# HFM_Can_AX_Eeprom_V1.net
KiCad netlist of a schematic drawn in Altium Designer
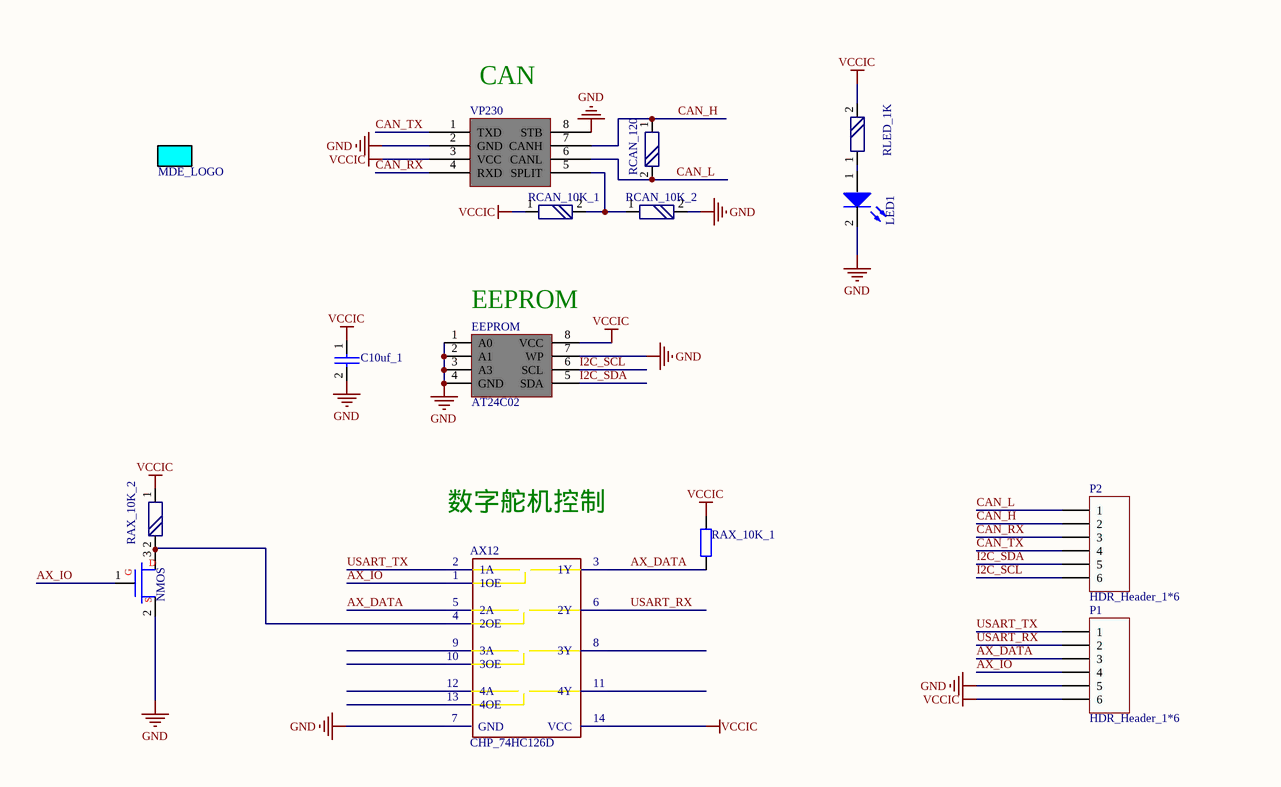
[diagram p0: HFM_Can_AX_Eeprom_V1.SchDoc, left]
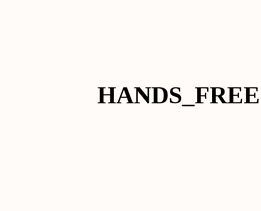
[diagram p1: HFM_Can_AX_Eeprom_V1.SchDoc, right]

(export (version "E")
  (design (tool "Eeschema 10.0.6"))
  (components
    (comp (ref "*")
      (value "MDE_LOGO")
      (footprint "MDE_LOGO_Overlay")
      (libsource (lib "Hands_free") (part "MDE_LOGO"))
    )
    (comp (ref "AX12")
      (value "CHP_74HC126D")
      (footprint "CHP_SOP_14P")
      (description "4路三态门缓冲器")
      (libsource (lib "HANDS-FREEE-PcbLib-V1.01") (part "CHP_74HC126D"))
    )
    (comp (ref "C10uf_1")
      (value "ELE_Cap_10uf")
      (footprint "ELE_0805_P")
      (description "电容10uf固定")
      (libsource (lib "HANDS-FREEE-PcbLib-V1.01") (part "ELE_Cap_10uf"))
    )
    (comp (ref "EEPROM")
      (value "AT24C02")
      (footprint "CHP_SOP_8P")
      (description "Polarized Capacitor (Radial)")
      (fields (field (name "PUBLISHER") "Altium Limited"))
      (libsource (lib "Hands_free") (part "CHP_AT24C0X"))
    )
    (comp (ref "LED1")
      (value "ELE_LED")
      (footprint "ELE_0805极性_P")
      (description "发光二极管")
      (fields (field (name "PUBLISHER") "Altium Limited"))
      (libsource (lib "Hands_free") (part "ELE_LED"))
    )
    (comp (ref "NMOS")
      (value "SIS412DN")
      (footprint "CHP_SOT23_P_3P")
      (description "MOS管")
      (fields (field (name "PUBLISHER") "Altium Limited"))
      (libsource (lib "Hands_free") (part "ELE_NMOS_1"))
    )
    (comp (ref "P1")
      (value "HDR_Header_1*6")
      (footprint "HDR_STAMPHOLE_2.00_DH_1*6")
      (fields (field (name "PUBLISHER") "Altium Limited"))
      (libsource (lib "HANDS-FREEE-PcbLib-V1.01") (part "HDR_Header_1*6"))
    )
    (comp (ref "P2")
      (value "HDR_Header_1*6")
      (footprint "HDR_STAMPHOLE_2.00_DH_1*6")
      (fields (field (name "PUBLISHER") "Altium Limited"))
      (libsource (lib "HANDS-FREEE-PcbLib-V1.01") (part "HDR_Header_1*6"))
    )
    (comp (ref "RAX_10K_1")
      (value "Res2")
      (footprint "ELE_0805_P")
      (description "Resistor")
      (fields (field (name "PUBLISHER") "Altium Limited"))
      (libsource (lib "Miscellaneous Devices") (part "Res2"))
    )
    (comp (ref "RAX_10K_2")
      (value "ELE_RES_1")
      (footprint "ELE_0805_P")
      (description "电阻")
      (libsource (lib "Hands_free") (part "ELE_RES_1"))
    )
    (comp (ref "RCAN_10K_1")
      (value "ELE_RES_1")
      (footprint "ELE_0805_P")
      (description "电阻")
      (libsource (lib "Hands_free") (part "ELE_RES_1"))
    )
    (comp (ref "RCAN_10K_2")
      (value "ELE_RES_1")
      (footprint "ELE_0805_P")
      (description "电阻")
      (libsource (lib "Hands_free") (part "ELE_RES_1"))
    )
    (comp (ref "RCAN_120")
      (value "ELE_RES_1")
      (footprint "ELE_0805_P")
      (description "电阻")
      (libsource (lib "Hands_free") (part "ELE_RES_1"))
    )
    (comp (ref "RLED_1K")
      (value "ELE_RES_1")
      (footprint "ELE_0805_P")
      (description "电阻")
      (libsource (lib "Hands_free") (part "ELE_RES_1"))
    )
    (comp (ref "VP230")
      (value "CHP_VP230_P")
      (footprint "CHP_VP230_P")
      (libsource (lib "Hands_free") (part "CHP_VP230_P"))
    )
  )
  (nets
    (net (code "1") (name "/AX_DATA") (class "Default")
      (node (ref "AX12") (pin "3") (pinfunction "1Y_3") (pintype "passive"))
      (node (ref "AX12") (pin "5") (pinfunction "2A_5") (pintype "passive"))
      (node (ref "P1") (pin "3") (pinfunction "3_3") (pintype "passive"))
      (node (ref "RAX_10K_1") (pin "1") (pinfunction "1_1") (pintype "passive"))
    )
    (net (code "2") (name "/AX_IO") (class "Default")
      (node (ref "AX12") (pin "1") (pinfunction "1OE_1") (pintype "passive"))
      (node (ref "NMOS") (pin "1") (pinfunction "G_1") (pintype "passive"))
      (node (ref "P1") (pin "4") (pinfunction "4_4") (pintype "passive"))
    )
    (net (code "3") (name "/CAN_H") (class "Default")
      (node (ref "P2") (pin "2") (pinfunction "2_2") (pintype "passive"))
      (node (ref "RCAN_120") (pin "1") (pintype "passive"))
      (node (ref "VP230") (pin "7") (pinfunction "CANH_7") (pintype "passive"))
    )
    (net (code "4") (name "/CAN_L") (class "Default")
      (node (ref "P2") (pin "1") (pinfunction "1_1") (pintype "passive"))
      (node (ref "RCAN_120") (pin "2") (pintype "passive"))
      (node (ref "VP230") (pin "6") (pinfunction "CANL_6") (pintype "passive"))
    )
    (net (code "5") (name "/CAN_RX") (class "Default")
      (node (ref "P2") (pin "3") (pinfunction "3_3") (pintype "passive"))
      (node (ref "VP230") (pin "4") (pinfunction "RXD_4") (pintype "passive"))
    )
    (net (code "6") (name "/CAN_TX") (class "Default")
      (node (ref "P2") (pin "4") (pinfunction "4_4") (pintype "passive"))
      (node (ref "VP230") (pin "1") (pinfunction "TXD_1") (pintype "passive"))
    )
    (net (code "7") (name "/I2C_SCL") (class "Default")
      (node (ref "EEPROM") (pin "6") (pinfunction "SCL_6") (pintype "passive"))
      (node (ref "P2") (pin "6") (pinfunction "6_6") (pintype "passive"))
    )
    (net (code "8") (name "/I2C_SDA") (class "Default")
      (node (ref "EEPROM") (pin "5") (pinfunction "SDA_5") (pintype "passive"))
      (node (ref "P2") (pin "5") (pinfunction "5_5") (pintype "passive"))
    )
    (net (code "9") (name "/USART_RX") (class "Default")
      (node (ref "AX12") (pin "6") (pinfunction "2Y_6") (pintype "passive"))
      (node (ref "P1") (pin "2") (pinfunction "2_2") (pintype "passive"))
    )
    (net (code "10") (name "/USART_TX") (class "Default")
      (node (ref "AX12") (pin "2") (pinfunction "1A_2") (pintype "passive"))
      (node (ref "P1") (pin "1") (pinfunction "1_1") (pintype "passive"))
    )
    (net (code "11") (name "GND") (class "Default")
      (node (ref "AX12") (pin "7") (pinfunction "GND_7") (pintype "passive"))
      (node (ref "C10uf_1") (pin "2") (pintype "passive"))
      (node (ref "EEPROM") (pin "1") (pinfunction "A0_1") (pintype "passive"))
      (node (ref "EEPROM") (pin "2") (pinfunction "A1_2") (pintype "passive"))
      (node (ref "EEPROM") (pin "3") (pinfunction "A3_3") (pintype "passive"))
      (node (ref "EEPROM") (pin "4") (pinfunction "GND_4") (pintype "passive"))
      (node (ref "EEPROM") (pin "7") (pinfunction "WP_7") (pintype "passive"))
      (node (ref "LED1") (pin "2") (pintype "passive"))
      (node (ref "NMOS") (pin "2") (pinfunction "S_2") (pintype "passive"))
      (node (ref "P1") (pin "5") (pinfunction "5_5") (pintype "passive"))
      (node (ref "RCAN_10K_2") (pin "2") (pintype "passive"))
      (node (ref "VP230") (pin "2") (pinfunction "GND_2") (pintype "passive"))
      (node (ref "VP230") (pin "8") (pinfunction "STB_8") (pintype "passive"))
    )
    (net (code "12") (name "Net-(AX12-2OE)") (class "Default")
      (node (ref "AX12") (pin "4") (pinfunction "2OE_4") (pintype "passive"))
      (node (ref "NMOS") (pin "3") (pinfunction "D_3") (pintype "passive"))
      (node (ref "RAX_10K_2") (pin "2") (pintype "passive"))
    )
    (net (code "13") (name "Net-(LED1-Pad1)") (class "Default")
      (node (ref "LED1") (pin "1") (pintype "passive"))
      (node (ref "RLED_1K") (pin "1") (pintype "passive"))
    )
    (net (code "14") (name "Net-(VP230-SPLIT)") (class "Default")
      (node (ref "RCAN_10K_1") (pin "2") (pintype "passive"))
      (node (ref "RCAN_10K_2") (pin "1") (pintype "passive"))
      (node (ref "VP230") (pin "5") (pinfunction "SPLIT_5") (pintype "passive"))
    )
    (net (code "15") (name "VCCIC") (class "Default")
      (node (ref "AX12") (pin "14") (pinfunction "VCC_14") (pintype "passive"))
      (node (ref "C10uf_1") (pin "1") (pintype "passive"))
      (node (ref "EEPROM") (pin "8") (pinfunction "VCC_8") (pintype "passive"))
      (node (ref "P1") (pin "6") (pinfunction "6_6") (pintype "passive"))
      (node (ref "RAX_10K_1") (pin "2") (pinfunction "2_2") (pintype "passive"))
      (node (ref "RAX_10K_2") (pin "1") (pintype "passive"))
      (node (ref "RCAN_10K_1") (pin "1") (pintype "passive"))
      (node (ref "RLED_1K") (pin "2") (pintype "passive"))
      (node (ref "VP230") (pin "3") (pinfunction "VCC_3") (pintype "passive"))
    )
    (net (code "16") (name "unconnected-(AX12-3A-Pad9)") (class "Default")
      (node (ref "AX12") (pin "9") (pinfunction "3A_9") (pintype "passive"))
    )
    (net (code "17") (name "unconnected-(AX12-3OE-Pad10)") (class "Default")
      (node (ref "AX12") (pin "10") (pinfunction "3OE_10") (pintype "passive"))
    )
    (net (code "18") (name "unconnected-(AX12-3Y-Pad8)") (class "Default")
      (node (ref "AX12") (pin "8") (pinfunction "3Y_8") (pintype "passive"))
    )
    (net (code "19") (name "unconnected-(AX12-4A-Pad12)") (class "Default")
      (node (ref "AX12") (pin "12") (pinfunction "4A_12") (pintype "passive"))
    )
    (net (code "20") (name "unconnected-(AX12-4OE-Pad13)") (class "Default")
      (node (ref "AX12") (pin "13") (pinfunction "4OE_13") (pintype "passive"))
    )
    (net (code "21") (name "unconnected-(AX12-4Y-Pad11)") (class "Default")
      (node (ref "AX12") (pin "11") (pinfunction "4Y_11") (pintype "passive"))
    )
  )
)
